# Dev21.net
KiCad netlist of a schematic drawn in EAGLE
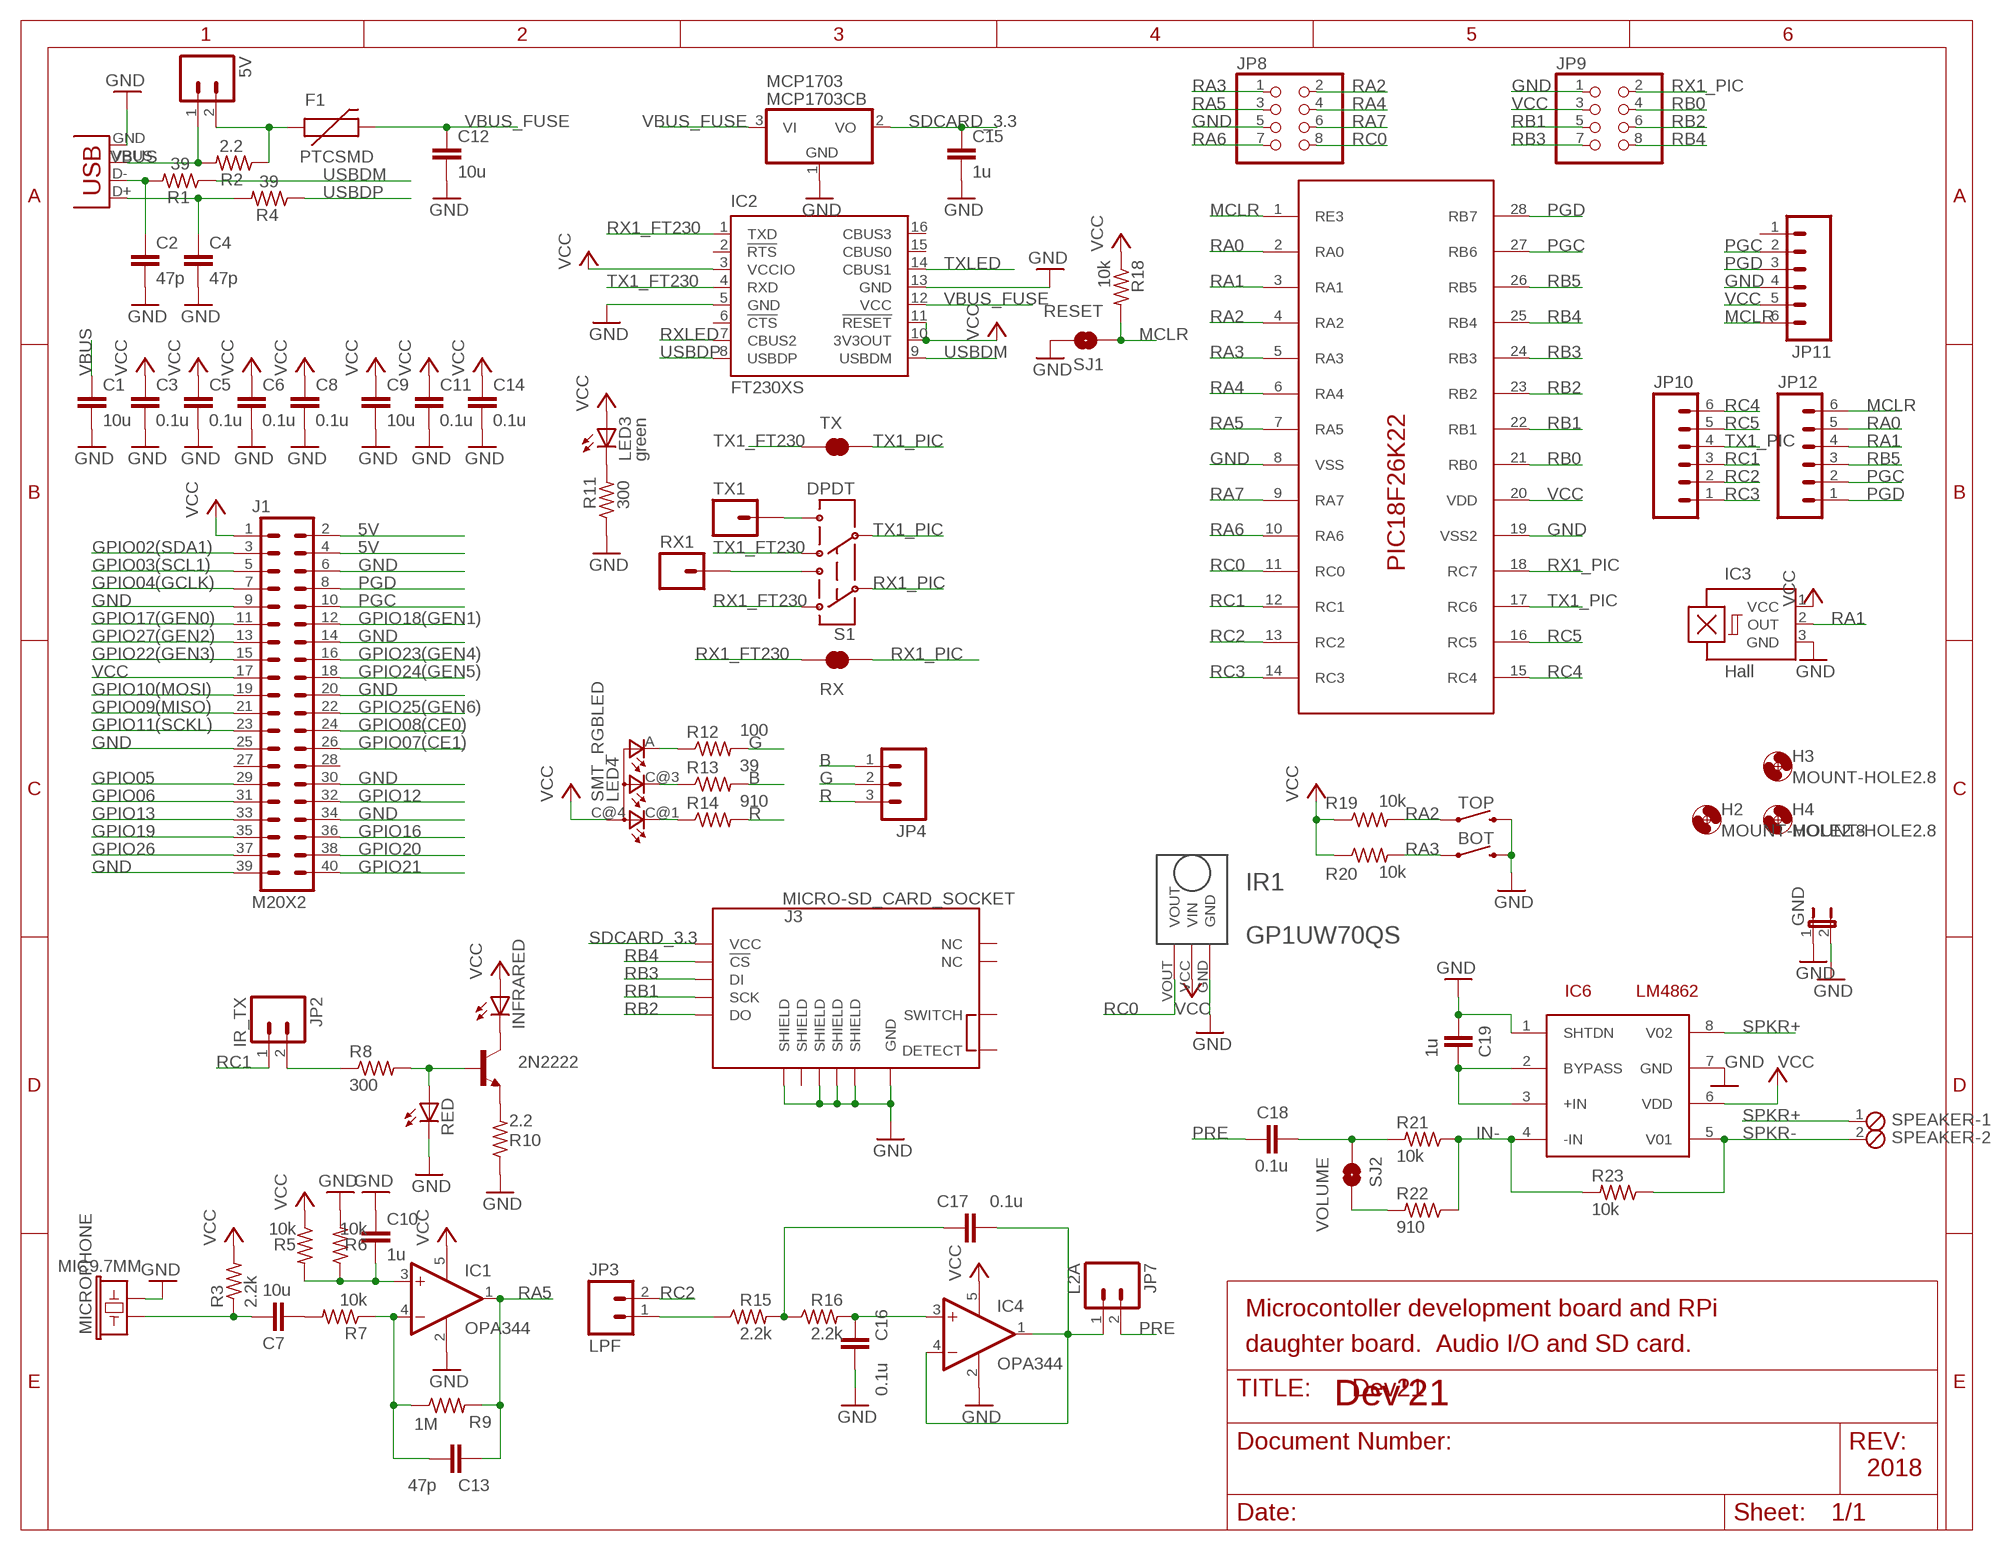
[diagram p0: schematic, sheet 1]

(export (version "E")
  (design (tool "Eeschema 10.0.6"))
  (components
    (comp (ref "2N2222")
      (value "TRANSISTOR_NPNSOT23-3")
      (footprint "eagle-import:SOT23-3")
      (libsource (lib "eagle-import") (part "TRANSISTOR_NPNSOT23-3"))
    )
    (comp (ref "5V")
      (value "M02LOCK")
      (footprint "eagle-import:1X02_LOCK")
      (libsource (lib "eagle-import") (part "M02LOCK"))
    )
    (comp (ref "BOT")
      (value "MOMENTARY-SWITCH-SPST-SMD-5.2MM")
      (footprint "eagle-import:TACTILE_SWITCH_SMD_5.2MM")
      (libsource (lib "eagle-import") (part "MOMENTARY-SWITCH-SPST-SMD-5.2MM"))
    )
    (comp (ref "C1")
      (value "10u")
      (footprint "eagle-import:C1206")
      (libsource (lib "eagle-import") (part "C-EUC1206"))
    )
    (comp (ref "C2")
      (value "47p")
      (footprint "eagle-import:C1206")
      (libsource (lib "eagle-import") (part "C-EUC1206"))
    )
    (comp (ref "C3")
      (value "0.1u")
      (footprint "eagle-import:C1206")
      (libsource (lib "eagle-import") (part "C-EUC1206"))
    )
    (comp (ref "C4")
      (value "47p")
      (footprint "eagle-import:C1206")
      (libsource (lib "eagle-import") (part "C-EUC1206"))
    )
    (comp (ref "C5")
      (value "0.1u")
      (footprint "eagle-import:C1206")
      (libsource (lib "eagle-import") (part "C-EUC1206"))
    )
    (comp (ref "C6")
      (value "0.1u")
      (footprint "eagle-import:C1206")
      (libsource (lib "eagle-import") (part "C-EUC1206"))
    )
    (comp (ref "C7")
      (value "10u")
      (footprint "eagle-import:C1206")
      (libsource (lib "eagle-import") (part "C-EUC1206"))
    )
    (comp (ref "C8")
      (value "0.1u")
      (footprint "eagle-import:C1206")
      (libsource (lib "eagle-import") (part "C-EUC1206"))
    )
    (comp (ref "C9")
      (value "10u")
      (footprint "eagle-import:C1206")
      (libsource (lib "eagle-import") (part "C-EUC1206"))
    )
    (comp (ref "C10")
      (value "1u")
      (footprint "eagle-import:C1206")
      (libsource (lib "eagle-import") (part "C-EUC1206"))
    )
    (comp (ref "C11")
      (value "0.1u")
      (footprint "eagle-import:C1206")
      (libsource (lib "eagle-import") (part "C-EUC1206"))
    )
    (comp (ref "C12")
      (value "10u")
      (footprint "eagle-import:C1206")
      (libsource (lib "eagle-import") (part "C-EUC1206"))
    )
    (comp (ref "C13")
      (value "47p")
      (footprint "eagle-import:C1206")
      (libsource (lib "eagle-import") (part "C-EUC1206"))
    )
    (comp (ref "C14")
      (value "0.1u")
      (footprint "eagle-import:C1206")
      (libsource (lib "eagle-import") (part "C-EUC1206"))
    )
    (comp (ref "C15")
      (value "1u")
      (footprint "eagle-import:C1206")
      (libsource (lib "eagle-import") (part "C-EUC1206"))
    )
    (comp (ref "C16")
      (value "0.1u")
      (footprint "eagle-import:C1206")
      (libsource (lib "eagle-import") (part "C-EUC1206"))
    )
    (comp (ref "C17")
      (value "0.1u")
      (footprint "eagle-import:C1206")
      (libsource (lib "eagle-import") (part "C-EUC1206"))
    )
    (comp (ref "C18")
      (value "0.1u")
      (footprint "eagle-import:C1206")
      (libsource (lib "eagle-import") (part "C-EUC1206"))
    )
    (comp (ref "C19")
      (value "1u")
      (footprint "eagle-import:C1206")
      (libsource (lib "eagle-import") (part "C-EUC1206"))
    )
    (comp (ref "F1")
      (value "PTCSMD")
      (footprint "eagle-import:PTC-1206")
      (libsource (lib "eagle-import") (part "PTCSMD"))
    )
    (comp (ref "GND")
      (value "JP1E")
      (footprint "eagle-import:JP1")
      (libsource (lib "eagle-import") (part "JP1E"))
    )
    (comp (ref "H2")
      (value "MOUNT-HOLE2.8")
      (footprint "eagle-import:2,8")
      (libsource (lib "eagle-import") (part "MOUNT-HOLE2.8"))
    )
    (comp (ref "H3")
      (value "MOUNT-HOLE2.8")
      (footprint "eagle-import:2,8")
      (libsource (lib "eagle-import") (part "MOUNT-HOLE2.8"))
    )
    (comp (ref "H4")
      (value "MOUNT-HOLE2.8")
      (footprint "eagle-import:2,8")
      (libsource (lib "eagle-import") (part "MOUNT-HOLE2.8"))
    )
    (comp (ref "IC1")
      (value "OPA344")
      (footprint "eagle-import:SOT23-5")
      (libsource (lib "eagle-import") (part "OPA-SOT23344N"))
    )
    (comp (ref "IC2")
      (value "FT230XS")
      (footprint "eagle-import:SSOP16")
      (libsource (lib "eagle-import") (part "FT230XS"))
    )
    (comp (ref "IC3")
      (value "Hall")
      (footprint "eagle-import:SOT23-W")
      (libsource (lib "eagle-import") (part "A12?LH02"))
    )
    (comp (ref "IC4")
      (value "OPA344")
      (footprint "eagle-import:SOT23-5")
      (libsource (lib "eagle-import") (part "OPA-SOT23344N"))
    )
    (comp (ref "IC6")
      (value "LM4862")
      (footprint "eagle-import:SO08")
      (libsource (lib "eagle-import") (part "LM4862"))
    )
    (comp (ref "INFRARED")
      (value "LED1206")
      (footprint "eagle-import:LED-1206")
      (libsource (lib "eagle-import") (part "LED1206"))
    )
    (comp (ref "IR1")
      (value "GP1UW70QS")
      (footprint "eagle-import:GP1UW70QS")
      (libsource (lib "eagle-import") (part "GP1UW70QS"))
    )
    (comp (ref "J1")
      (value "M20X2")
      (footprint "eagle-import:2X20")
      (libsource (lib "eagle-import") (part "M20X2"))
    )
    (comp (ref "J3")
      (value "MICRO-SD_CARD_SOCKET")
      (footprint "eagle-import:MICRO-SD-SOCKET")
      (libsource (lib "eagle-import") (part "MICRO-SD_CARD_SOCKET"))
    )
    (comp (ref "JP2")
      (value "IR_TX")
      (footprint "eagle-import:1X02_LOCK")
      (libsource (lib "eagle-import") (part "M02LOCK"))
    )
    (comp (ref "JP3")
      (value "LPF")
      (footprint "eagle-import:1X02_LOCK")
      (libsource (lib "eagle-import") (part "M02LOCK"))
    )
    (comp (ref "JP4")
      (value "M03LOCK")
      (footprint "eagle-import:1X03_LOCK")
      (libsource (lib "eagle-import") (part "M03LOCK"))
    )
    (comp (ref "JP7")
      (value "L2A")
      (footprint "eagle-import:1X02_LOCK")
      (libsource (lib "eagle-import") (part "M02LOCK"))
    )
    (comp (ref "JP8")
      (value "PINHD-2X4")
      (footprint "eagle-import:2X04")
      (libsource (lib "eagle-import") (part "PINHD-2X4"))
    )
    (comp (ref "JP9")
      (value "PINHD-2X4")
      (footprint "eagle-import:2X04")
      (libsource (lib "eagle-import") (part "PINHD-2X4"))
    )
    (comp (ref "JP10")
      (value "M06LOCK")
      (footprint "eagle-import:1X06_LOCK")
      (libsource (lib "eagle-import") (part "M06LOCK"))
    )
    (comp (ref "JP11")
      (value "M06LOCK")
      (footprint "eagle-import:1X06_LOCK")
      (libsource (lib "eagle-import") (part "M06LOCK"))
    )
    (comp (ref "JP12")
      (value "M06LOCK")
      (footprint "eagle-import:1X06_LOCK")
      (libsource (lib "eagle-import") (part "M06LOCK"))
    )
    (comp (ref "LED3")
      (value "green")
      (footprint "eagle-import:LED-1206")
      (libsource (lib "eagle-import") (part "LED1206"))
    )
    (comp (ref "LED4")
      (value "SMT_RGBLED")
      (footprint "eagle-import:P-LCC-4")
      (libsource (lib "eagle-import") (part "SMT_RGBLED"))
    )
    (comp (ref "MCP1703")
      (value "MCP1703CB")
      (footprint "eagle-import:SOT23")
      (libsource (lib "eagle-import") (part "MCP1703CB"))
    )
    (comp (ref "MICROPHONE")
      (value "MIC9.7MM")
      (footprint "eagle-import:MIC-9.7MM")
      (libsource (lib "eagle-import") (part "MIC9.7MM"))
    )
    (comp (ref "PIC18F26K22")
      (value "PIC18F26J2228SSOP")
      (footprint "eagle-import:SSOP28DB")
      (libsource (lib "eagle-import") (part "PIC18F26J2228SSOP"))
    )
    (comp (ref "R1")
      (value "39")
      (footprint "eagle-import:R1206")
      (libsource (lib "eagle-import") (part "R-US_R1206"))
    )
    (comp (ref "R2")
      (value "2.2")
      (footprint "eagle-import:R1206")
      (libsource (lib "eagle-import") (part "R-US_R1206"))
    )
    (comp (ref "R3")
      (value "2.2k")
      (footprint "eagle-import:R1206")
      (libsource (lib "eagle-import") (part "R-US_R1206"))
    )
    (comp (ref "R4")
      (value "39")
      (footprint "eagle-import:R1206")
      (libsource (lib "eagle-import") (part "R-US_R1206"))
    )
    (comp (ref "R5")
      (value "10k")
      (footprint "eagle-import:R1206")
      (libsource (lib "eagle-import") (part "R-US_R1206"))
    )
    (comp (ref "R6")
      (value "10k")
      (footprint "eagle-import:R1206")
      (libsource (lib "eagle-import") (part "R-US_R1206"))
    )
    (comp (ref "R7")
      (value "10k")
      (footprint "eagle-import:R1206")
      (libsource (lib "eagle-import") (part "R-US_R1206"))
    )
    (comp (ref "R8")
      (value "300")
      (footprint "eagle-import:R1206")
      (libsource (lib "eagle-import") (part "R-US_R1206"))
    )
    (comp (ref "R9")
      (value "1M")
      (footprint "eagle-import:R1206")
      (libsource (lib "eagle-import") (part "R-US_R1206"))
    )
    (comp (ref "R10")
      (value "2.2")
      (footprint "eagle-import:R1206")
      (libsource (lib "eagle-import") (part "R-US_R1206"))
    )
    (comp (ref "R11")
      (value "300")
      (footprint "eagle-import:R1206")
      (libsource (lib "eagle-import") (part "R-US_R1206"))
    )
    (comp (ref "R12")
      (value "100")
      (footprint "eagle-import:R1206")
      (libsource (lib "eagle-import") (part "R-US_R1206"))
    )
    (comp (ref "R13")
      (value "39")
      (footprint "eagle-import:R1206")
      (libsource (lib "eagle-import") (part "R-US_R1206"))
    )
    (comp (ref "R14")
      (value "910")
      (footprint "eagle-import:R1206")
      (libsource (lib "eagle-import") (part "R-US_R1206"))
    )
    (comp (ref "R15")
      (value "2.2k")
      (footprint "eagle-import:R1206")
      (libsource (lib "eagle-import") (part "R-US_R1206"))
    )
    (comp (ref "R16")
      (value "2.2k")
      (footprint "eagle-import:R1206")
      (libsource (lib "eagle-import") (part "R-US_R1206"))
    )
    (comp (ref "R18")
      (value "10k")
      (footprint "eagle-import:R1206")
      (libsource (lib "eagle-import") (part "R-US_R1206"))
    )
    (comp (ref "R19")
      (value "10k")
      (footprint "eagle-import:R1206")
      (libsource (lib "eagle-import") (part "R-US_R1206"))
    )
    (comp (ref "R20")
      (value "10k")
      (footprint "eagle-import:R1206")
      (libsource (lib "eagle-import") (part "R-US_R1206"))
    )
    (comp (ref "R21")
      (value "10k")
      (footprint "eagle-import:R1206")
      (libsource (lib "eagle-import") (part "R-US_R1206"))
    )
    (comp (ref "R22")
      (value "910")
      (footprint "eagle-import:R1206")
      (libsource (lib "eagle-import") (part "R-US_R1206"))
    )
    (comp (ref "R23")
      (value "10k")
      (footprint "eagle-import:R1206")
      (libsource (lib "eagle-import") (part "R-US_R1206"))
    )
    (comp (ref "RED")
      (value "LED1206")
      (footprint "eagle-import:LED-1206")
      (libsource (lib "eagle-import") (part "LED1206"))
    )
    (comp (ref "RX")
      (value "SJ_NC")
      (footprint "eagle-import:SMT-JUMPER_2_NC_TRACE_NO-SILK")
      (libsource (lib "eagle-import") (part "JUMPER-SMT_2_NC_TRACE_NO-SILK"))
    )
    (comp (ref "RX1")
      (value "M01PTH")
      (footprint "eagle-import:1X01")
      (libsource (lib "eagle-import") (part "M01PTH"))
    )
    (comp (ref "S1")
      (value "DPDT")
      (footprint "eagle-import:AYZ0202")
      (libsource (lib "eagle-import") (part "SWITCH-DPDTAYZ0202"))
    )
    (comp (ref "SJ1")
      (value "RESET")
      (footprint "eagle-import:SJ_2S-NOTRACE")
      (libsource (lib "eagle-import") (part "SOLDERJUMPERNC2"))
    )
    (comp (ref "SJ2")
      (value "VOLUME")
      (footprint "eagle-import:SJ_2S-NOTRACE")
      (libsource (lib "eagle-import") (part "SOLDERJUMPERNC2"))
    )
    (comp (ref "SPEAKER")
      (value "MPT2")
      (footprint "eagle-import:2POL254")
      (libsource (lib "eagle-import") (part "MPT2"))
    )
    (comp (ref "TOP")
      (value "MOMENTARY-SWITCH-SPST-SMD-5.2MM")
      (footprint "eagle-import:TACTILE_SWITCH_SMD_5.2MM")
      (libsource (lib "eagle-import") (part "MOMENTARY-SWITCH-SPST-SMD-5.2MM"))
    )
    (comp (ref "TX")
      (value "SJ_NC")
      (footprint "eagle-import:SMT-JUMPER_2_NC_TRACE_NO-SILK")
      (libsource (lib "eagle-import") (part "JUMPER-SMT_2_NC_TRACE_NO-SILK"))
    )
    (comp (ref "TX1")
      (value "M01PTH")
      (footprint "eagle-import:1X01")
      (libsource (lib "eagle-import") (part "M01PTH"))
    )
    (comp (ref "X1")
      (value "USBSMD")
      (footprint "eagle-import:USB-MINIB")
      (libsource (lib "eagle-import") (part "USBSMD"))
    )
  )
  (nets
    (net (code "1") (name "/5V") (class "Default")
      (node (ref "J1") (pin "2") (pinfunction "2_2") (pintype "passive"))
      (node (ref "J1") (pin "4") (pinfunction "4_4") (pintype "passive"))
    )
    (net (code "2") (name "/B") (class "Default")
      (node (ref "JP4") (pin "1") (pinfunction "1_1") (pintype "passive"))
      (node (ref "R13") (pin "2") (pinfunction "2_2") (pintype "passive"))
    )
    (net (code "3") (name "/G") (class "Default")
      (node (ref "JP4") (pin "2") (pinfunction "2_2") (pintype "passive"))
      (node (ref "R12") (pin "2") (pinfunction "2_2") (pintype "passive"))
    )
    (net (code "4") (name "/GPIO02(SDA1)") (class "Default")
      (node (ref "J1") (pin "3") (pinfunction "3_3") (pintype "passive"))
    )
    (net (code "5") (name "/GPIO03(SCL1)") (class "Default")
      (node (ref "J1") (pin "5") (pinfunction "5_5") (pintype "passive"))
    )
    (net (code "6") (name "/GPIO04(GCLK)") (class "Default")
      (node (ref "J1") (pin "7") (pinfunction "7_7") (pintype "passive"))
    )
    (net (code "7") (name "/GPIO05") (class "Default")
      (node (ref "J1") (pin "29") (pinfunction "29_29") (pintype "passive"))
    )
    (net (code "8") (name "/GPIO06") (class "Default")
      (node (ref "J1") (pin "31") (pinfunction "31_31") (pintype "passive"))
    )
    (net (code "9") (name "/GPIO07(CE1)") (class "Default")
      (node (ref "J1") (pin "26") (pinfunction "26_26") (pintype "passive"))
    )
    (net (code "10") (name "/GPIO08(CE0)") (class "Default")
      (node (ref "J1") (pin "24") (pinfunction "24_24") (pintype "passive"))
    )
    (net (code "11") (name "/GPIO09(MISO)") (class "Default")
      (node (ref "J1") (pin "21") (pinfunction "21_21") (pintype "passive"))
    )
    (net (code "12") (name "/GPIO10(MOSI)") (class "Default")
      (node (ref "J1") (pin "19") (pinfunction "19_19") (pintype "passive"))
    )
    (net (code "13") (name "/GPIO11(SCKL)") (class "Default")
      (node (ref "J1") (pin "23") (pinfunction "23_23") (pintype "passive"))
    )
    (net (code "14") (name "/GPIO12") (class "Default")
      (node (ref "J1") (pin "32") (pinfunction "32_32") (pintype "passive"))
    )
    (net (code "15") (name "/GPIO13") (class "Default")
      (node (ref "J1") (pin "33") (pinfunction "33_33") (pintype "passive"))
    )
    (net (code "16") (name "/GPIO16") (class "Default")
      (node (ref "J1") (pin "36") (pinfunction "36_36") (pintype "passive"))
    )
    (net (code "17") (name "/GPIO17(GEN0)") (class "Default")
      (node (ref "J1") (pin "11") (pinfunction "11_11") (pintype "passive"))
    )
    (net (code "18") (name "/GPIO18(GEN1)") (class "Default")
      (node (ref "J1") (pin "12") (pinfunction "12_12") (pintype "passive"))
    )
    (net (code "19") (name "/GPIO19") (class "Default")
      (node (ref "J1") (pin "35") (pinfunction "35_35") (pintype "passive"))
    )
    (net (code "20") (name "/GPIO20") (class "Default")
      (node (ref "J1") (pin "38") (pinfunction "38_38") (pintype "passive"))
    )
    (net (code "21") (name "/GPIO21") (class "Default")
      (node (ref "J1") (pin "40") (pinfunction "40_40") (pintype "passive"))
    )
    (net (code "22") (name "/GPIO22(GEN3)") (class "Default")
      (node (ref "J1") (pin "15") (pinfunction "15_15") (pintype "passive"))
    )
    (net (code "23") (name "/GPIO23(GEN4)") (class "Default")
      (node (ref "J1") (pin "16") (pinfunction "16_16") (pintype "passive"))
    )
    (net (code "24") (name "/GPIO24(GEN5)") (class "Default")
      (node (ref "J1") (pin "18") (pinfunction "18_18") (pintype "passive"))
    )
    (net (code "25") (name "/GPIO25(GEN6)") (class "Default")
      (node (ref "J1") (pin "22") (pinfunction "22_22") (pintype "passive"))
    )
    (net (code "26") (name "/GPIO26") (class "Default")
      (node (ref "J1") (pin "37") (pinfunction "37_37") (pintype "passive"))
    )
    (net (code "27") (name "/GPIO27(GEN2)") (class "Default")
      (node (ref "J1") (pin "13") (pinfunction "13_13") (pintype "passive"))
    )
    (net (code "28") (name "/IN-") (class "Default")
      (node (ref "IC6") (pin "4") (pinfunction "-IN_4") (pintype "bidirectional"))
      (node (ref "R21") (pin "1") (pinfunction "1_1") (pintype "passive"))
      (node (ref "R22") (pin "1") (pinfunction "1_1") (pintype "passive"))
      (node (ref "R23") (pin "2") (pinfunction "2_2") (pintype "passive"))
    )
    (net (code "29") (name "/MCLR") (class "Default")
      (node (ref "JP11") (pin "6") (pinfunction "6_6") (pintype "passive"))
      (node (ref "JP12") (pin "6") (pinfunction "6_6") (pintype "passive"))
      (node (ref "PIC18F26K22") (pin "1") (pinfunction "RE3_1") (pintype "bidirectional"))
      (node (ref "R18") (pin "2") (pinfunction "2_2") (pintype "passive"))
      (node (ref "SJ1") (pin "1") (pinfunction "1_1") (pintype "passive"))
    )
    (net (code "30") (name "/PGC") (class "Default")
      (node (ref "J1") (pin "10") (pinfunction "10_10") (pintype "passive"))
      (node (ref "JP11") (pin "2") (pinfunction "2_2") (pintype "passive"))
      (node (ref "JP12") (pin "2") (pinfunction "2_2") (pintype "passive"))
      (node (ref "PIC18F26K22") (pin "27") (pinfunction "RB6_27") (pintype "bidirectional"))
    )
    (net (code "31") (name "/PGD") (class "Default")
      (node (ref "J1") (pin "8") (pinfunction "8_8") (pintype "passive"))
      (node (ref "JP11") (pin "3") (pinfunction "3_3") (pintype "passive"))
      (node (ref "JP12") (pin "1") (pinfunction "1_1") (pintype "passive"))
      (node (ref "PIC18F26K22") (pin "28") (pinfunction "RB7_28") (pintype "bidirectional"))
    )
    (net (code "32") (name "/PRE") (class "Default")
      (node (ref "C18") (pin "2") (pinfunction "2_2") (pintype "passive"))
      (node (ref "JP7") (pin "2") (pinfunction "2_2") (pintype "passive"))
    )
    (net (code "33") (name "/R") (class "Default")
      (node (ref "JP4") (pin "3") (pinfunction "3_3") (pintype "passive"))
      (node (ref "R14") (pin "2") (pinfunction "2_2") (pintype "passive"))
    )
    (net (code "34") (name "/RA0") (class "Default")
      (node (ref "JP12") (pin "5") (pinfunction "5_5") (pintype "passive"))
      (node (ref "PIC18F26K22") (pin "2") (pinfunction "RA0_2") (pintype "bidirectional"))
    )
    (net (code "35") (name "/RA1") (class "Default")
      (node (ref "IC3") (pin "2") (pinfunction "OUT_2") (pintype "output"))
      (node (ref "JP12") (pin "4") (pinfunction "4_4") (pintype "passive"))
      (node (ref "PIC18F26K22") (pin "3") (pinfunction "RA1_3") (pintype "bidirectional"))
    )
    (net (code "36") (name "/RA2") (class "Default")
      (node (ref "JP8") (pin "2") (pinfunction "2_2") (pintype "passive"))
      (node (ref "PIC18F26K22") (pin "4") (pinfunction "RA2_4") (pintype "bidirectional"))
      (node (ref "R19") (pin "2") (pinfunction "2_2") (pintype "passive"))
      (node (ref "TOP") (pin "1") (pinfunction "1_1") (pintype "passive"))
    )
    (net (code "37") (name "/RA3") (class "Default")
      (node (ref "BOT") (pin "1") (pinfunction "1_1") (pintype "passive"))
      (node (ref "JP8") (pin "1") (pinfunction "1_1") (pintype "passive"))
      (node (ref "PIC18F26K22") (pin "5") (pinfunction "RA3_5") (pintype "bidirectional"))
      (node (ref "R20") (pin "2") (pinfunction "2_2") (pintype "passive"))
    )
    (net (code "38") (name "/RA4") (class "Default")
      (node (ref "JP8") (pin "4") (pinfunction "4_4") (pintype "passive"))
      (node (ref "PIC18F26K22") (pin "6") (pinfunction "RA4_6") (pintype "bidirectional"))
    )
    (net (code "39") (name "/RA5") (class "Default")
      (node (ref "C13") (pin "2") (pinfunction "2_2") (pintype "passive"))
      (node (ref "IC1") (pin "1") (pinfunction "OUT_1") (pintype "output"))
      (node (ref "JP8") (pin "3") (pinfunction "3_3") (pintype "passive"))
      (node (ref "PIC18F26K22") (pin "7") (pinfunction "RA5_7") (pintype "bidirectional"))
      (node (ref "R9") (pin "2") (pinfunction "2_2") (pintype "passive"))
    )
    (net (code "40") (name "/RA6") (class "Default")
      (node (ref "JP8") (pin "7") (pinfunction "7_7") (pintype "passive"))
      (node (ref "PIC18F26K22") (pin "10") (pinfunction "RA6_10") (pintype "bidirectional"))
    )
    (net (code "41") (name "/RA7") (class "Default")
      (node (ref "JP8") (pin "6") (pinfunction "6_6") (pintype "passive"))
      (node (ref "PIC18F26K22") (pin "9") (pinfunction "RA7_9") (pintype "bidirectional"))
    )
    (net (code "42") (name "/RB0") (class "Default")
      (node (ref "JP9") (pin "4") (pinfunction "4_4") (pintype "passive"))
      (node (ref "PIC18F26K22") (pin "21") (pinfunction "RB0_21") (pintype "bidirectional"))
    )
    (net (code "43") (name "/RB1") (class "Default")
      (node (ref "J3") (pin "SCLK") (pinfunction "SCK_SCLK") (pintype "bidirectional"))
      (node (ref "JP9") (pin "5") (pinfunction "5_5") (pintype "passive"))
      (node (ref "PIC18F26K22") (pin "22") (pinfunction "RB1_22") (pintype "bidirectional"))
    )
    (net (code "44") (name "/RB2") (class "Default")
      (node (ref "J3") (pin "DO") (pinfunction "DO_DO") (pintype "bidirectional"))
      (node (ref "JP9") (pin "6") (pinfunction "6_6") (pintype "passive"))
      (node (ref "PIC18F26K22") (pin "23") (pinfunction "RB2_23") (pintype "bidirectional"))
    )
    (net (code "45") (name "/RB3") (class "Default")
      (node (ref "J3") (pin "DI") (pinfunction "DI_DI") (pintype "bidirectional"))
      (node (ref "JP9") (pin "7") (pinfunction "7_7") (pintype "passive"))
      (node (ref "PIC18F26K22") (pin "24") (pinfunction "RB3_24") (pintype "bidirectional"))
    )
    (net (code "46") (name "/RB4") (class "Default")
      (node (ref "J3") (pin "CS") (pinfunction "~{CS}_CS") (pintype "bidirectional"))
      (node (ref "JP9") (pin "8") (pinfunction "8_8") (pintype "passive"))
      (node (ref "PIC18F26K22") (pin "25") (pinfunction "RB4_25") (pintype "bidirectional"))
    )
    (net (code "47") (name "/RB5") (class "Default")
      (node (ref "JP12") (pin "3") (pinfunction "3_3") (pintype "passive"))
      (node (ref "PIC18F26K22") (pin "26") (pinfunction "RB5_26") (pintype "bidirectional"))
    )
    (net (code "48") (name "/RC0") (class "Default")
      (node (ref "IR1") (pin "VOUT") (pinfunction "VOUT_VOUT") (pintype "bidirectional"))
      (node (ref "JP8") (pin "8") (pinfunction "8_8") (pintype "passive"))
      (node (ref "PIC18F26K22") (pin "11") (pinfunction "RC0_11") (pintype "bidirectional"))
    )
    (net (code "49") (name "/RC1") (class "Default")
      (node (ref "JP10") (pin "3") (pinfunction "3_3") (pintype "passive"))
      (node (ref "JP2") (pin "1") (pinfunction "1_1") (pintype "passive"))
      (node (ref "PIC18F26K22") (pin "12") (pinfunction "RC1_12") (pintype "bidirectional"))
    )
    (net (code "50") (name "/RC2") (class "Default")
      (node (ref "JP10") (pin "2") (pinfunction "2_2") (pintype "passive"))
      (node (ref "JP3") (pin "2") (pinfunction "2_2") (pintype "passive"))
      (node (ref "PIC18F26K22") (pin "13") (pinfunction "RC2_13") (pintype "bidirectional"))
    )
    (net (code "51") (name "/RC3") (class "Default")
      (node (ref "JP10") (pin "1") (pinfunction "1_1") (pintype "passive"))
      (node (ref "PIC18F26K22") (pin "14") (pinfunction "RC3_14") (pintype "bidirectional"))
    )
    (net (code "52") (name "/RC4") (class "Default")
      (node (ref "JP10") (pin "6") (pinfunction "6_6") (pintype "passive"))
      (node (ref "PIC18F26K22") (pin "15") (pinfunction "RC4_15") (pintype "bidirectional"))
    )
    (net (code "53") (name "/RC5") (class "Default")
      (node (ref "JP10") (pin "5") (pinfunction "5_5") (pintype "passive"))
      (node (ref "PIC18F26K22") (pin "16") (pinfunction "RC5_16") (pintype "bidirectional"))
    )
    (net (code "54") (name "/RX1_FT230") (class "Default")
      (node (ref "IC2") (pin "1") (pinfunction "TXD_1") (pintype "output"))
      (node (ref "RX") (pin "1") (pinfunction "1_1") (pintype "passive"))
      (node (ref "S1") (pin "1") (pinfunction "1_1") (pintype "bidirectional"))
    )
    (net (code "55") (name "/RX1_PIC") (class "Default")
      (node (ref "JP9") (pin "2") (pinfunction "2_2") (pintype "passive"))
      (node (ref "PIC18F26K22") (pin "18") (pinfunction "RC7_18") (pintype "bidirectional"))
      (node (ref "RX") (pin "2") (pinfunction "2_2") (pintype "passive"))
      (node (ref "S1") (pin "2") (pinfunction "2_2") (pintype "bidirectional"))
    )
    (net (code "56") (name "/RXLED") (class "Default")
      (node (ref "IC2") (pin "7") (pinfunction "CBUS2_7") (pintype "bidirectional"))
    )
    (net (code "57") (name "/SDCARD_3.3") (class "Default")
      (node (ref "C15") (pin "1") (pinfunction "1_1") (pintype "passive"))
      (node (ref "J3") (pin "VCC") (pinfunction "VCC_VCC") (pintype "bidirectional"))
      (node (ref "MCP1703") (pin "2") (pinfunction "VO_2") (pintype "passive"))
    )
    (net (code "58") (name "/SPKR+") (class "Default")
      (node (ref "IC6") (pin "8") (pinfunction "V02_8") (pintype "bidirectional"))
      (node (ref "SPEAKER") (pin "1") (pinfunction "1_1") (pintype "passive"))
    )
    (net (code "59") (name "/SPKR-") (class "Default")
      (node (ref "IC6") (pin "5") (pinfunction "V01_5") (pintype "bidirectional"))
      (node (ref "R23") (pin "1") (pinfunction "1_1") (pintype "passive"))
      (node (ref "SPEAKER") (pin "2") (pinfunction "1_2") (pintype "passive"))
    )
    (net (code "60") (name "/TX1_FT230") (class "Default")
      (node (ref "IC2") (pin "4") (pinfunction "RXD_4") (pintype "input"))
      (node (ref "S1") (pin "4") (pinfunction "4_4") (pintype "bidirectional"))
      (node (ref "TX") (pin "1") (pinfunction "1_1") (pintype "passive"))
    )
    (net (code "61") (name "/TX1_PIC") (class "Default")
      (node (ref "JP10") (pin "4") (pinfunction "4_4") (pintype "passive"))
      (node (ref "PIC18F26K22") (pin "17") (pinfunction "RC6_17") (pintype "bidirectional"))
      (node (ref "S1") (pin "5") (pinfunction "5_5") (pintype "bidirectional"))
      (node (ref "TX") (pin "2") (pinfunction "2_2") (pintype "passive"))
    )
    (net (code "62") (name "/TXLED") (class "Default")
      (node (ref "IC2") (pin "14") (pinfunction "CBUS1_14") (pintype "bidirectional"))
    )
    (net (code "63") (name "/USBDM") (class "Default")
      (node (ref "IC2") (pin "9") (pinfunction "USBDM_9") (pintype "input"))
      (node (ref "R1") (pin "1") (pinfunction "1_1") (pintype "passive"))
    )
    (net (code "64") (name "/USBDP") (class "Default")
      (node (ref "IC2") (pin "8") (pinfunction "USBDP_8") (pintype "input"))
      (node (ref "R4") (pin "1") (pinfunction "1_1") (pintype "passive"))
    )
    (net (code "65") (name "/VBUS") (class "Default")
      (node (ref "5V") (pin "1") (pinfunction "1_1") (pintype "passive"))
      (node (ref "C1") (pin "1") (pinfunction "1_1") (pintype "passive"))
      (node (ref "R2") (pin "2") (pinfunction "2_2") (pintype "passive"))
      (node (ref "X1") (pin "VBUS") (pinfunction "VBUS_VBUS") (pintype "bidirectional"))
    )
    (net (code "66") (name "/VBUS_FUSE") (class "Default")
      (node (ref "C12") (pin "1") (pinfunction "1_1") (pintype "passive"))
      (node (ref "F1") (pin "2") (pinfunction "2_2") (pintype "bidirectional"))
      (node (ref "IC2") (pin "12") (pinfunction "VCC_12") (pintype "power_in"))
      (node (ref "MCP1703") (pin "3") (pinfunction "VI_3") (pintype "input"))
    )
    (net (code "67") (name "GND") (class "Default")
      (node (ref "BOT") (pin "3") (pinfunction "2_3") (pintype "passive"))
      (node (ref "C1") (pin "2") (pinfunction "2_2") (pintype "passive"))
      (node (ref "C10") (pin "1") (pinfunction "1_1") (pintype "passive"))
      (node (ref "C11") (pin "2") (pinfunction "2_2") (pintype "passive"))
      (node (ref "C12") (pin "2") (pinfunction "2_2") (pintype "passive"))
      (node (ref "C14") (pin "2") (pinfunction "2_2") (pintype "passive"))
      (node (ref "C15") (pin "2") (pinfunction "2_2") (pintype "passive"))
      (node (ref "C16") (pin "1") (pinfunction "1_1") (pintype "passive"))
      (node (ref "C19") (pin "2") (pinfunction "2_2") (pintype "passive"))
      (node (ref "C2") (pin "2") (pinfunction "2_2") (pintype "passive"))
      (node (ref "C3") (pin "2") (pinfunction "2_2") (pintype "passive"))
      (node (ref "C4") (pin "2") (pinfunction "2_2") (pintype "passive"))
      (node (ref "C5") (pin "2") (pinfunction "2_2") (pintype "passive"))
      (node (ref "C6") (pin "2") (pinfunction "2_2") (pintype "passive"))
      (node (ref "C8") (pin "2") (pinfunction "2_2") (pintype "passive"))
      (node (ref "C9") (pin "2") (pinfunction "2_2") (pintype "passive"))
      (node (ref "GND") (pin "1") (pinfunction "1_1") (pintype "passive"))
      (node (ref "GND") (pin "2") (pinfunction "2_2") (pintype "passive"))
      (node (ref "IC1") (pin "2") (pinfunction "V-_2") (pintype "power_in"))
      (node (ref "IC2") (pin "13") (pinfunction "GND_13") (pintype "power_in"))
      (node (ref "IC2") (pin "5") (pinfunction "GND_5") (pintype "power_in"))
      (node (ref "IC3") (pin "3") (pinfunction "GND_3") (pintype "power_in"))
      (node (ref "IC4") (pin "2") (pinfunction "V-_2") (pintype "power_in"))
      (node (ref "IC6") (pin "1") (pinfunction "SHTDN_1") (pintype "bidirectional"))
      (node (ref "IC6") (pin "7") (pinfunction "GND_7") (pintype "power_in"))
      (node (ref "IR1") (pin "GND") (pinfunction "GND_GND") (pintype "bidirectional"))
      (node (ref "J1") (pin "14") (pinfunction "14_14") (pintype "passive"))
      (node (ref "J1") (pin "20") (pinfunction "20_20") (pintype "passive"))
      (node (ref "J1") (pin "25") (pinfunction "25_25") (pintype "passive"))
      (node (ref "J1") (pin "30") (pinfunction "30_30") (pintype "passive"))
      (node (ref "J1") (pin "34") (pinfunction "34_34") (pintype "passive"))
      (node (ref "J1") (pin "39") (pinfunction "39_39") (pintype "passive"))
      (node (ref "J1") (pin "6") (pinfunction "6_6") (pintype "passive"))
      (node (ref "J1") (pin "9") (pinfunction "9_9") (pintype "passive"))
      (node (ref "J3") (pin "GND") (pinfunction "GND_GND") (pintype "bidirectional"))
      (node (ref "J3") (pin "SHIELD1") (pinfunction "SHIELD_SHIELD1") (pintype "bidirectional"))
      (node (ref "J3") (pin "SHIELD3") (pinfunction "SHIELD_SHIELD3") (pintype "bidirectional"))
      (node (ref "J3") (pin "SHIELD4") (pinfunction "SHIELD_SHIELD4") (pintype "bidirectional"))
      (node (ref "J3") (pin "SHIELD5") (pinfunction "SHIELD_SHIELD5") (pintype "bidirectional"))
      (node (ref "JP11") (pin "4") (pinfunction "4_4") (pintype "passive"))
      (node (ref "JP8") (pin "5") (pinfunction "5_5") (pintype "passive"))
      (node (ref "JP9") (pin "1") (pinfunction "1_1") (pintype "passive"))
      (node (ref "MCP1703") (pin "1") (pinfunction "GND_1") (pintype "passive"))
      (node (ref "MICROPHONE") (pin "2") (pinfunction "2_2") (pintype "passive"))
      (node (ref "PIC18F26K22") (pin "19") (pinfunction "VSS2_19") (pintype "bidirectional"))
      (node (ref "PIC18F26K22") (pin "8") (pinfunction "VSS_8") (pintype "bidirectional"))
      (node (ref "R10") (pin "1") (pinfunction "1_1") (pintype "passive"))
      (node (ref "R11") (pin "1") (pinfunction "1_1") (pintype "passive"))
      (node (ref "R6") (pin "2") (pinfunction "2_2") (pintype "passive"))
      (node (ref "RED") (pin "C") (pinfunction "C_C") (pintype "passive"))
      (node (ref "SJ1") (pin "2") (pinfunction "2_2") (pintype "passive"))
      (node (ref "TOP") (pin "3") (pinfunction "2_3") (pintype "passive"))
      (node (ref "X1") (pin "GND") (pinfunction "GND_GND") (pintype "bidirectional"))
    )
    (net (code "68") (name "Net-(2N2222-B)") (class "Default")
      (node (ref "2N2222") (pin "1") (pinfunction "B_1") (pintype "passive"))
      (node (ref "R8") (pin "2") (pinfunction "2_2") (pintype "passive"))
      (node (ref "RED") (pin "A") (pinfunction "A_A") (pintype "passive"))
    )
    (net (code "69") (name "Net-(2N2222-C)") (class "Default")
      (node (ref "2N2222") (pin "3") (pinfunction "C_3") (pintype "passive"))
      (node (ref "INFRARED") (pin "C") (pinfunction "C_C") (pintype "passive"))
    )
    (net (code "70") (name "Net-(2N2222-E)") (class "Default")
      (node (ref "2N2222") (pin "2") (pinfunction "E_2") (pintype "passive"))
      (node (ref "R10") (pin "2") (pinfunction "2_2") (pintype "passive"))
    )
    (net (code "71") (name "Net-(5V-Pad2)") (class "Default")
      (node (ref "5V") (pin "2") (pinfunction "2_2") (pintype "passive"))
      (node (ref "F1") (pin "1") (pinfunction "1_1") (pintype "bidirectional"))
      (node (ref "R2") (pin "1") (pinfunction "1_1") (pintype "passive"))
    )
    (net (code "72") (name "Net-(C2-Pad1)") (class "Default")
      (node (ref "C2") (pin "1") (pinfunction "1_1") (pintype "passive"))
      (node (ref "R1") (pin "2") (pinfunction "2_2") (pintype "passive"))
      (node (ref "X1") (pin "D-") (pinfunction "D-_D-") (pintype "bidirectional"))
    )
    (net (code "73") (name "Net-(C4-Pad1)") (class "Default")
      (node (ref "C4") (pin "1") (pinfunction "1_1") (pintype "passive"))
      (node (ref "R4") (pin "2") (pinfunction "2_2") (pintype "passive"))
      (node (ref "X1") (pin "D+") (pinfunction "D+_D+") (pintype "bidirectional"))
    )
    (net (code "74") (name "Net-(C7-Pad1)") (class "Default")
      (node (ref "C7") (pin "1") (pinfunction "1_1") (pintype "passive"))
      (node (ref "MICROPHONE") (pin "1") (pinfunction "1_1") (pintype "passive"))
      (node (ref "R3") (pin "1") (pinfunction "1_1") (pintype "passive"))
    )
    (net (code "75") (name "Net-(C7-Pad2)") (class "Default")
      (node (ref "C7") (pin "2") (pinfunction "2_2") (pintype "passive"))
      (node (ref "R7") (pin "2") (pinfunction "2_2") (pintype "passive"))
    )
    (net (code "76") (name "Net-(C17-Pad2)") (class "Default")
      (node (ref "C17") (pin "2") (pinfunction "2_2") (pintype "passive"))
      (node (ref "R15") (pin "2") (pinfunction "2_2") (pintype "passive"))
      (node (ref "R16") (pin "1") (pinfunction "1_1") (pintype "passive"))
    )
    (net (code "77") (name "Net-(C18-Pad1)") (class "Default")
      (node (ref "C18") (pin "1") (pinfunction "1_1") (pintype "passive"))
      (node (ref "R21") (pin "2") (pinfunction "2_2") (pintype "passive"))
      (node (ref "SJ2") (pin "1") (pinfunction "1_1") (pintype "passive"))
    )
    (net (code "78") (name "Net-(IC1-+IN)") (class "Default")
      (node (ref "C10") (pin "2") (pinfunction "2_2") (pintype "passive"))
      (node (ref "IC1") (pin "3") (pinfunction "+IN_3") (pintype "input"))
      (node (ref "R5") (pin "2") (pinfunction "2_2") (pintype "passive"))
      (node (ref "R6") (pin "1") (pinfunction "1_1") (pintype "passive"))
    )
    (net (code "79") (name "Net-(IC1--IN)") (class "Default")
      (node (ref "C13") (pin "1") (pinfunction "1_1") (pintype "passive"))
      (node (ref "IC1") (pin "4") (pinfunction "-IN_4") (pintype "input"))
      (node (ref "R7") (pin "1") (pinfunction "1_1") (pintype "passive"))
      (node (ref "R9") (pin "1") (pinfunction "1_1") (pintype "passive"))
    )
    (net (code "80") (name "Net-(IC4-+IN)") (class "Default")
      (node (ref "C16") (pin "2") (pinfunction "2_2") (pintype "passive"))
      (node (ref "IC4") (pin "3") (pinfunction "+IN_3") (pintype "input"))
      (node (ref "R16") (pin "2") (pinfunction "2_2") (pintype "passive"))
    )
    (net (code "81") (name "Net-(IC4--IN)") (class "Default")
      (node (ref "C17") (pin "1") (pinfunction "1_1") (pintype "passive"))
      (node (ref "IC4") (pin "1") (pinfunction "OUT_1") (pintype "output"))
      (node (ref "IC4") (pin "4") (pinfunction "-IN_4") (pintype "input"))
      (node (ref "JP7") (pin "1") (pinfunction "1_1") (pintype "passive"))
    )
    (net (code "82") (name "Net-(IC6-+IN)") (class "Default")
      (node (ref "C19") (pin "1") (pinfunction "1_1") (pintype "passive"))
      (node (ref "IC6") (pin "2") (pinfunction "BYPASS_2") (pintype "bidirectional"))
      (node (ref "IC6") (pin "3") (pinfunction "+IN_3") (pintype "bidirectional"))
    )
    (net (code "83") (name "Net-(JP2-Pad2)") (class "Default")
      (node (ref "JP2") (pin "2") (pinfunction "2_2") (pintype "passive"))
      (node (ref "R8") (pin "1") (pinfunction "1_1") (pintype "passive"))
    )
    (net (code "84") (name "Net-(JP3-Pad1)") (class "Default")
      (node (ref "JP3") (pin "1") (pinfunction "1_1") (pintype "passive"))
      (node (ref "R15") (pin "1") (pinfunction "1_1") (pintype "passive"))
    )
    (net (code "85") (name "Net-(LED3-PadC)") (class "Default")
      (node (ref "LED3") (pin "C") (pinfunction "C_C") (pintype "passive"))
      (node (ref "R11") (pin "2") (pinfunction "2_2") (pintype "passive"))
    )
    (net (code "86") (name "Net-(LED4-CBLUE)") (class "Default")
      (node (ref "LED4") (pin "C@3") (pinfunction "CBLUE_C@3") (pintype "passive"))
      (node (ref "R13") (pin "1") (pinfunction "1_1") (pintype "passive"))
    )
    (net (code "87") (name "Net-(LED4-CGREEN)") (class "Default")
      (node (ref "LED4") (pin "A") (pinfunction "CGREEN_A") (pintype "passive"))
      (node (ref "R12") (pin "1") (pinfunction "1_1") (pintype "passive"))
    )
    (net (code "88") (name "Net-(LED4-CRED)") (class "Default")
      (node (ref "LED4") (pin "C@1") (pinfunction "CRED_C@1") (pintype "passive"))
      (node (ref "R14") (pin "1") (pinfunction "1_1") (pintype "passive"))
    )
    (net (code "89") (name "Net-(R22-Pad2)") (class "Default")
      (node (ref "R22") (pin "2") (pinfunction "2_2") (pintype "passive"))
      (node (ref "SJ2") (pin "2") (pinfunction "2_2") (pintype "passive"))
    )
    (net (code "90") (name "Net-(RX1-Pad1)") (class "Default")
      (node (ref "RX1") (pin "1") (pinfunction "1_1") (pintype "passive"))
      (node (ref "S1") (pin "3") (pinfunction "3_3") (pintype "bidirectional"))
    )
    (net (code "91") (name "Net-(S1-Pad6)") (class "Default")
      (node (ref "S1") (pin "6") (pinfunction "6_6") (pintype "bidirectional"))
      (node (ref "TX1") (pin "1") (pinfunction "1_1") (pintype "passive"))
    )
    (net (code "92") (name "VCC") (class "Default")
      (node (ref "C11") (pin "1") (pinfunction "1_1") (pintype "passive"))
      (node (ref "C14") (pin "1") (pinfunction "1_1") (pintype "passive"))
      (node (ref "C3") (pin "1") (pinfunction "1_1") (pintype "passive"))
      (node (ref "C5") (pin "1") (pinfunction "1_1") (pintype "passive"))
      (node (ref "C6") (pin "1") (pinfunction "1_1") (pintype "passive"))
      (node (ref "C8") (pin "1") (pinfunction "1_1") (pintype "passive"))
      (node (ref "C9") (pin "1") (pinfunction "1_1") (pintype "passive"))
      (node (ref "IC1") (pin "5") (pinfunction "V+_5") (pintype "power_in"))
      (node (ref "IC2") (pin "10") (pinfunction "3V3OUT_10") (pintype "output"))
      (node (ref "IC2") (pin "11") (pinfunction "~{RESET}_11") (pintype "input"))
      (node (ref "IC2") (pin "3") (pinfunction "VCCIO_3") (pintype "power_in"))
      (node (ref "IC3") (pin "1") (pinfunction "VCC_1") (pintype "power_in"))
      (node (ref "IC4") (pin "5") (pinfunction "V+_5") (pintype "power_in"))
      (node (ref "IC6") (pin "6") (pinfunction "VDD_6") (pintype "power_in"))
      (node (ref "INFRARED") (pin "A") (pinfunction "A_A") (pintype "passive"))
      (node (ref "IR1") (pin "VCC") (pinfunction "VIN_VCC") (pintype "bidirectional"))
      (node (ref "J1") (pin "1") (pinfunction "1_1") (pintype "passive"))
      (node (ref "J1") (pin "17") (pinfunction "17_17") (pintype "passive"))
      (node (ref "JP11") (pin "5") (pinfunction "5_5") (pintype "passive"))
      (node (ref "JP9") (pin "3") (pinfunction "3_3") (pintype "passive"))
      (node (ref "LED3") (pin "A") (pinfunction "A_A") (pintype "passive"))
      (node (ref "LED4") (pin "C@4") (pinfunction "A_C@4") (pintype "passive"))
      (node (ref "PIC18F26K22") (pin "20") (pinfunction "VDD_20") (pintype "bidirectional"))
      (node (ref "R18") (pin "1") (pinfunction "1_1") (pintype "passive"))
      (node (ref "R19") (pin "1") (pinfunction "1_1") (pintype "passive"))
      (node (ref "R20") (pin "1") (pinfunction "1_1") (pintype "passive"))
      (node (ref "R3") (pin "2") (pinfunction "2_2") (pintype "passive"))
      (node (ref "R5") (pin "1") (pinfunction "1_1") (pintype "passive"))
    )
    (net (code "93") (name "unconnected-(IC2-CBUS0-Pad15)") (class "Default")
      (node (ref "IC2") (pin "15") (pinfunction "CBUS0_15") (pintype "bidirectional"))
    )
    (net (code "94") (name "unconnected-(IC2-CBUS3-Pad16)") (class "Default")
      (node (ref "IC2") (pin "16") (pinfunction "CBUS3_16") (pintype "bidirectional"))
    )
    (net (code "95") (name "unconnected-(IC2-~{CTS}-Pad6)") (class "Default")
      (node (ref "IC2") (pin "6") (pinfunction "~{CTS}_6") (pintype "input"))
    )
    (net (code "96") (name "unconnected-(IC2-~{RTS}-Pad2)") (class "Default")
      (node (ref "IC2") (pin "2") (pinfunction "~{RTS}_2") (pintype "output"))
    )
    (net (code "97") (name "unconnected-(J1-Pad27)") (class "Default")
      (node (ref "J1") (pin "27") (pinfunction "27_27") (pintype "passive"))
    )
    (net (code "98") (name "unconnected-(J1-Pad28)") (class "Default")
      (node (ref "J1") (pin "28") (pinfunction "28_28") (pintype "passive"))
    )
    (net (code "99") (name "unconnected-(J3-NC-PadNC1)") (class "Default")
      (node (ref "J3") (pin "NC1") (pinfunction "NC_NC1") (pintype "bidirectional"))
    )
    (net (code "100") (name "unconnected-(J3-NC-PadNC2)") (class "Default")
      (node (ref "J3") (pin "NC2") (pinfunction "NC_NC2") (pintype "bidirectional"))
    )
    (net (code "101") (name "unconnected-(J3-PadDETECT)") (class "Default")
      (node (ref "J3") (pin "DETECT") (pinfunction "DETECT_DETECT") (pintype "bidirectional"))
    )
    (net (code "102") (name "unconnected-(J3-PadSWITCH)") (class "Default")
      (node (ref "J3") (pin "SWITCH") (pinfunction "SWITCH_SWITCH") (pintype "bidirectional"))
    )
    (net (code "103") (name "unconnected-(J3-SHIELD-PadSHIELD2)") (class "Default")
      (node (ref "J3") (pin "SHIELD2") (pinfunction "SHIELD_SHIELD2") (pintype "bidirectional"))
    )
    (net (code "104") (name "unconnected-(JP11-Pad1)") (class "Default")
      (node (ref "JP11") (pin "1") (pinfunction "1_1") (pintype "passive"))
    )
  )
)
